# 86_ZigBee.net
KiCad netlist of a schematic drawn in Altium Designer
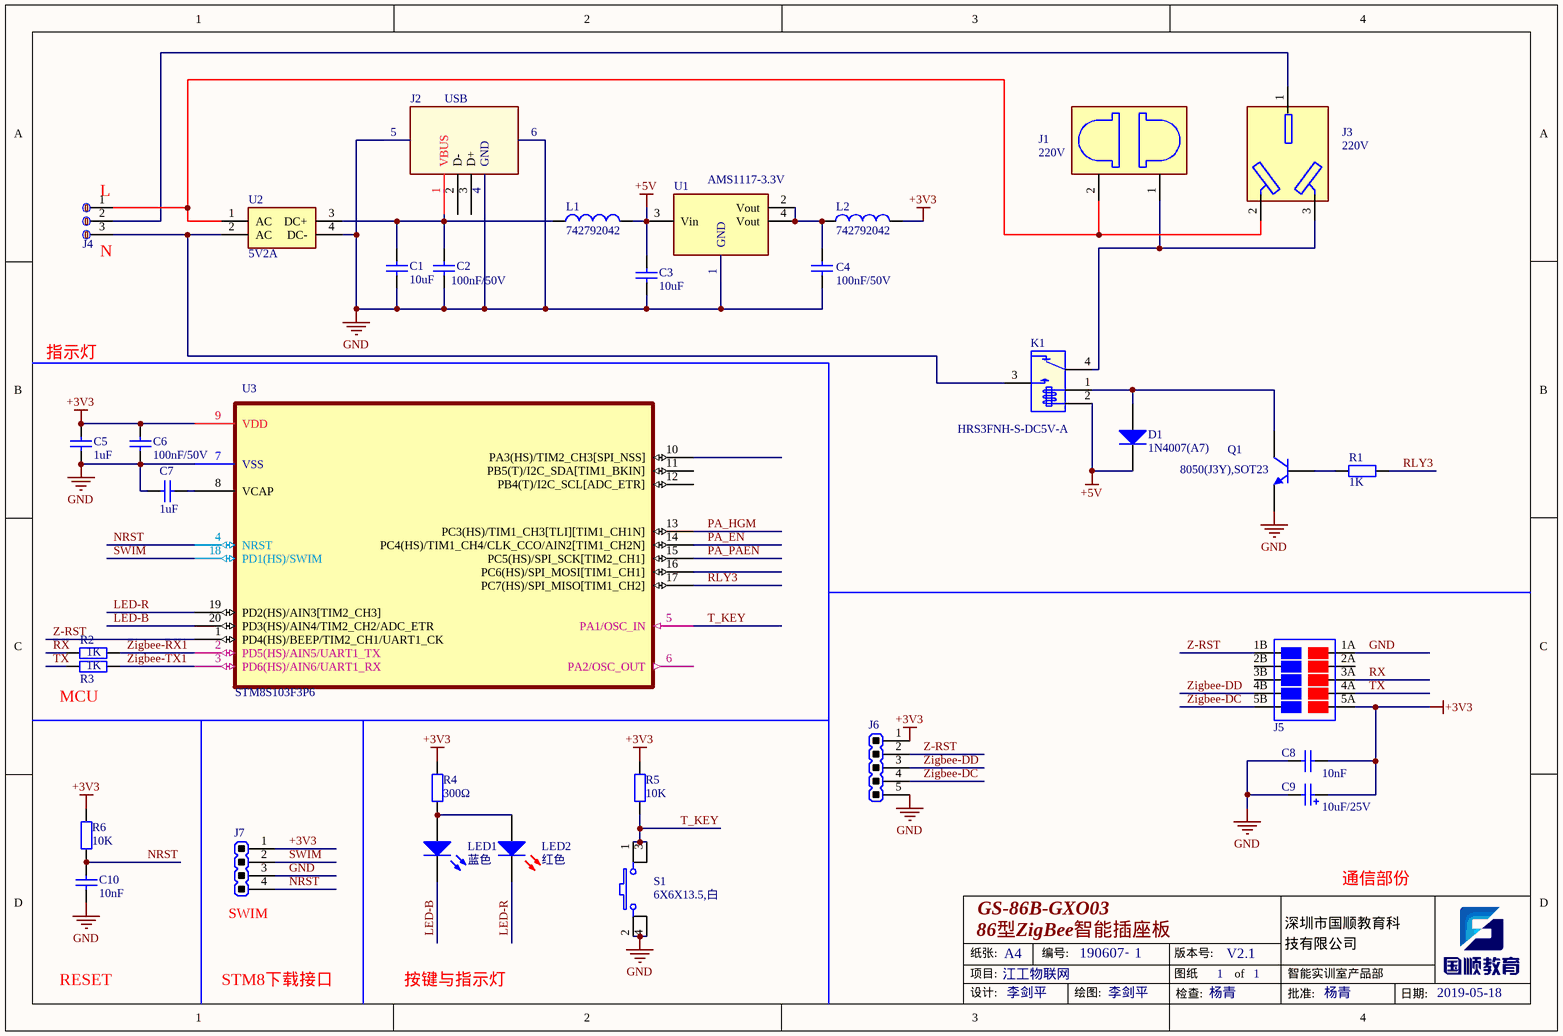
[diagram p0: 86型ZigBee智能插座.SchDoc]

(export (version "E")
  (design (tool "Eeschema 10.0.6"))
  (components
    (comp (ref "C1")
      (value "10uF")
      (footprint "C0603")
      (description "Capacitor")
      (libsource (lib "贴片电容") (part "10uF_16V_0603"))
    )
    (comp (ref "C2")
      (value "100nF/50V")
      (footprint "C0603")
      (description "Capacitor")
      (libsource (lib "贴片电容") (part "100nF_50V_0603"))
    )
    (comp (ref "C3")
      (value "10uF")
      (footprint "C0603")
      (description "Capacitor")
      (libsource (lib "贴片电容") (part "10uF_16V_0603"))
    )
    (comp (ref "C4")
      (value "100nF/50V")
      (footprint "C0603")
      (description "Capacitor")
      (libsource (lib "贴片电容") (part "100nF_50V_0603"))
    )
    (comp (ref "C5")
      (value "1uF")
      (footprint "C0603")
      (description "Capacitor")
      (libsource (lib "贴片电容") (part "1uF_25V_X7R_0603"))
    )
    (comp (ref "C6")
      (value "100nF/50V")
      (footprint "C0603")
      (description "Capacitor")
      (libsource (lib "贴片电容") (part "100nF_50V_0603"))
    )
    (comp (ref "C7")
      (value "1uF")
      (footprint "C0603")
      (description "Capacitor")
      (libsource (lib "贴片电容") (part "1uF_25V_X7R_0603"))
    )
    (comp (ref "C8")
      (value "10nF")
      (footprint "C0603")
      (description "Capacitor")
      (libsource (lib "贴片电容") (part "10nF_16V_0603"))
    )
    (comp (ref "C9")
      (value "10uF/25V")
      (footprint "TC3528X21B")
      (description "钽电容,10uF/25V-3528B")
      (libsource (lib "贴片电容") (part "CAPC-10uF/25V_3528B"))
    )
    (comp (ref "C10")
      (value "10nF")
      (footprint "C0603")
      (description "Capacitor")
      (libsource (lib "贴片电容") (part "10nF_16V_0603"))
    )
    (comp (ref "D1")
      (value "1N4007(A7)")
      (footprint "SOD-123FL")
      (description "1N4007(A7),1A/1000V,SOD-123FL")
      (libsource (lib "二极管") (part "1N4007(A7)_SOD-123FL"))
    )
    (comp (ref "J1")
      (value "220V")
      (footprint "JACK-2 Line")
      (description "PCB板电源插口")
      (libsource (lib "杂项元件") (part "JACK-2 Line"))
    )
    (comp (ref "J2")
      (value "USB")
      (footprint "USB-F-Type A")
      (description "USB-TYPE A 母座")
      (libsource (lib "连接器") (part "USB-AF-17.5"))
    )
    (comp (ref "J3")
      (value "220V")
      (footprint "JACK-3 Line")
      (description "PCB板电源插口")
      (libsource (lib "杂项元件") (part "JACK-3 Line"))
    )
    (comp (ref "J4")
      (value "PILLAR-3P-11.5-(6.5*4.5*8+G4.2*1.5*2)")
      (footprint "PILLAR-3P-11.5-(6.5*4.5*8+G4.2*1.5*2)")
      (description "铜柱接口")
      (libsource (lib "接口") (part "PILLAR-3P-11.5-(6.5*4.5*8+G4.2*1.5*2)"))
    )
    (comp (ref "J5")
      (value "EDGE 10P-2.54/1.0-F")
      (footprint "EDGE 10P-2.54/1.0-F")
      (description "金手指PCB焊接位")
      (libsource (lib "连接器") (part "EDGE 10P-2.54/1.0-F"))
    )
    (comp (ref "J6")
      (value "HDRM-1*5-2.54-AK")
      (footprint "HDRM-1*5-2.54-AK1")
      (description "排针,直")
      (libsource (lib "接口") (part "HDRM-1*5-2.54-AK"))
    )
    (comp (ref "J7")
      (value "HDRM-1*4-2.54-AK")
      (footprint "HDRM-1*4-2.54-AK1")
      (description "排针,直")
      (libsource (lib "接口") (part "HDRM-1*4-2.54-AK"))
    )
    (comp (ref "K1")
      (value "HRS3FNH-S-DC5V-A")
      (footprint "RELAY_HRS3FNH-S-DCxV-A")
      (description "汇港,HRS3FNH-S-DC5V-A,5V,4脚,容量10A,线圈功率0.45W")
      (libsource (lib "杂项元件") (part "RLY_HRS3FNH-S-DC5V-A"))
    )
    (comp (ref "L1")
      (value "742792042")
      (footprint "L0805")
      (description "磁珠,WE-CBF,600@100M,\r\n500Ohm,200mA,0805,742792042")
      (libsource (lib "电感") (part "BEAD-742792042_0805"))
    )
    (comp (ref "L2")
      (value "742792042")
      (footprint "L0805")
      (description "WE-CBF,600@100M,500Ohm,200mA,0805,742792042")
      (libsource (lib "") (part "BEAD-742792042_0805_1"))
    )
    (comp (ref "LED1")
      (value "蓝色")
      (footprint "LED0805-B1")
      (description "0805 LED")
      (libsource (lib "晶体管") (part "LED-蓝_0805"))
    )
    (comp (ref "LED2")
      (value "红色")
      (footprint "LED0805-R1")
      (description "0805 LED")
      (libsource (lib "晶体管") (part "LED-红_0805"))
    )
    (comp (ref "Q1")
      (value "8050(J3Y),SOT23")
      (footprint "SOT23")
      (description "NPN,8050,SOT23")
      (libsource (lib "三极管") (part "NPN_8050(J3Y)_SOT23"))
    )
    (comp (ref "R1")
      (value "1K")
      (footprint "R0603")
      (description "1K,±5%,0603")
      (libsource (lib "") (part "10K_5%_0603_1"))
    )
    (comp (ref "R2")
      (value "1K")
      (footprint "R0603")
      (description "1K,±5%,0603")
      (libsource (lib "贴片电阻") (part "1K_5%_0603"))
    )
    (comp (ref "R3")
      (value "1K")
      (footprint "R0603")
      (description "1K,±5%,0603")
      (libsource (lib "贴片电阻") (part "1K_5%_0603"))
    )
    (comp (ref "R4")
      (value "300Ω")
      (footprint "R0603")
      (description "300Ω,±5%,0603")
      (libsource (lib "贴片电阻") (part "300Ω_5%_0603"))
    )
    (comp (ref "R5")
      (value "10K")
      (footprint "R0603")
      (description "10K,±5%,0603")
      (libsource (lib "贴片电阻") (part "10K_5%_0603"))
    )
    (comp (ref "R6")
      (value "10K")
      (footprint "R0603")
      (description "10K,±5%,0603")
      (libsource (lib "贴片电阻") (part "10K_5%_0603"))
    )
    (comp (ref "S1")
      (value "6X6X13.5,白")
      (footprint "SW2-6.0X6.0X13.5-W")
      (description "6X6X13.5,白,插针")
      (libsource (lib "按键开关") (part "SW-PB_6X6X13.5-4P-W"))
    )
    (comp (ref "U1")
      (value "AMS1117-3.3V")
      (footprint "SOT-223")
      (description "三端稳压器")
      (libsource (lib "IC") (part "AMS1117-3.3V_SOT223"))
    )
    (comp (ref "U2")
      (value "5V2A")
      (footprint "Module_RPD10W")
      (description "AC/DC模块")
      (libsource (lib "杂项元件") (part "Module_RPD10W05E202S"))
    )
    (comp (ref "U3")
      (value "STM8S103F3P6")
      (footprint "TSSOP20-0.65/4.4")
      (description "STM8 ARM-based 32-bit MCU with 8 Kbytes Flash, 20-pin TSSOP, Industrial Temperature")
      (libsource (lib "IC") (part "STM8S103F3P6_TSSOP20"))
    )
  )
  (nets
    (net (code "1") (name "+3V3") (class "Default")
      (node (ref "C5") (pin "2") (pinfunction "2_2") (pintype "passive"))
      (node (ref "C6") (pin "1") (pinfunction "1_1") (pintype "passive"))
      (node (ref "C8") (pin "2") (pinfunction "2_2") (pintype "passive"))
      (node (ref "C9") (pin "1") (pinfunction "1_1") (pintype "passive"))
      (node (ref "J5") (pin "5A") (pinfunction "5A_5A") (pintype "passive"))
      (node (ref "J6") (pin "1") (pinfunction "1_1") (pintype "passive"))
      (node (ref "J7") (pin "1") (pinfunction "1_1") (pintype "passive"))
      (node (ref "L2") (pin "2") (pinfunction "2_2") (pintype "passive"))
      (node (ref "R4") (pin "2") (pinfunction "2_2") (pintype "passive"))
      (node (ref "R5") (pin "1") (pinfunction "1_1") (pintype "passive"))
      (node (ref "R6") (pin "1") (pinfunction "1_1") (pintype "passive"))
      (node (ref "U3") (pin "9") (pinfunction "VDD_9") (pintype "power_in"))
    )
    (net (code "2") (name "+5V") (class "Default")
      (node (ref "C3") (pin "1") (pinfunction "1_1") (pintype "passive"))
      (node (ref "D1") (pin "2") (pinfunction "K_2") (pintype "passive"))
      (node (ref "K1") (pin "2") (pinfunction "COIL2_2") (pintype "passive"))
      (node (ref "L1") (pin "2") (pinfunction "2_2") (pintype "passive"))
      (node (ref "U1") (pin "3") (pinfunction "Vin_3") (pintype "passive"))
    )
    (net (code "3") (name "/LED-B") (class "Default")
      (node (ref "LED1") (pin "2") (pinfunction "K_2") (pintype "passive"))
      (node (ref "U3") (pin "20") (pinfunction "PD3(HS)/AIN4/TIM2_CH2/ADC_ETR_20") (pintype "bidirectional"))
    )
    (net (code "4") (name "/LED-R") (class "Default")
      (node (ref "LED2") (pin "2") (pinfunction "K_2") (pintype "passive"))
      (node (ref "U3") (pin "19") (pinfunction "PD2(HS)/AIN3[TIM2_CH3]_19") (pintype "bidirectional"))
    )
    (net (code "5") (name "/NRST") (class "Default")
      (node (ref "C10") (pin "2") (pinfunction "2_2") (pintype "passive"))
      (node (ref "J7") (pin "4") (pinfunction "4_4") (pintype "passive"))
      (node (ref "R6") (pin "2") (pinfunction "2_2") (pintype "passive"))
      (node (ref "U3") (pin "4") (pinfunction "NRST_4") (pintype "bidirectional"))
    )
    (net (code "6") (name "/PA_EN") (class "Default")
      (node (ref "U3") (pin "14") (pinfunction "PC4(HS)/TIM1_CH4/CLK_CCO/AIN2[TIM1_CH2N]_14") (pintype "bidirectional"))
    )
    (net (code "7") (name "/PA_HGM") (class "Default")
      (node (ref "U3") (pin "13") (pinfunction "PC3(HS)/TIM1_CH3[TLI][TIM1_CH1N]_13") (pintype "bidirectional"))
    )
    (net (code "8") (name "/PA_PAEN") (class "Default")
      (node (ref "U3") (pin "15") (pinfunction "PC5(HS)/SPI_SCK[TIM2_CH1]_15") (pintype "bidirectional"))
    )
    (net (code "9") (name "/RLY3") (class "Default")
      (node (ref "R1") (pin "2") (pinfunction "2_2") (pintype "passive"))
      (node (ref "U3") (pin "17") (pinfunction "PC7(HS)/SPI_MISO[TIM1_CH2]_17") (pintype "bidirectional"))
    )
    (net (code "10") (name "/RX") (class "Default")
      (node (ref "J5") (pin "3A") (pinfunction "3A_3A") (pintype "passive"))
      (node (ref "R2") (pin "1") (pinfunction "1_1") (pintype "passive"))
    )
    (net (code "11") (name "/SWIM") (class "Default")
      (node (ref "J7") (pin "2") (pinfunction "2_2") (pintype "passive"))
      (node (ref "U3") (pin "18") (pinfunction "PD1(HS)/SWIM_18") (pintype "bidirectional"))
    )
    (net (code "12") (name "/TX") (class "Default")
      (node (ref "J5") (pin "4A") (pinfunction "4A_4A") (pintype "passive"))
      (node (ref "R3") (pin "1") (pinfunction "1_1") (pintype "passive"))
    )
    (net (code "13") (name "/T_KEY") (class "Default")
      (node (ref "R5") (pin "2") (pinfunction "2_2") (pintype "passive"))
      (node (ref "S1") (pin "1") (pinfunction "1_1") (pintype "passive"))
      (node (ref "S1") (pin "3") (pinfunction "3_3") (pintype "passive"))
      (node (ref "U3") (pin "5") (pinfunction "PA1/OSC_IN_5") (pintype "input"))
    )
    (net (code "14") (name "/Z-RST") (class "Default")
      (node (ref "J5") (pin "1B") (pinfunction "1B_1B") (pintype "passive"))
      (node (ref "J6") (pin "2") (pinfunction "2_2") (pintype "passive"))
      (node (ref "U3") (pin "1") (pinfunction "PD4(HS)/BEEP/TIM2_CH1/UART1_CK_1") (pintype "bidirectional"))
    )
    (net (code "15") (name "/Zigbee-DC") (class "Default")
      (node (ref "J5") (pin "5B") (pinfunction "5B_5B") (pintype "passive"))
      (node (ref "J6") (pin "4") (pinfunction "4_4") (pintype "passive"))
    )
    (net (code "16") (name "/Zigbee-DD") (class "Default")
      (node (ref "J5") (pin "4B") (pinfunction "4B_4B") (pintype "passive"))
      (node (ref "J6") (pin "3") (pinfunction "3_3") (pintype "passive"))
    )
    (net (code "17") (name "/Zigbee-RX1") (class "Default")
      (node (ref "R2") (pin "2") (pinfunction "2_2") (pintype "passive"))
      (node (ref "U3") (pin "2") (pinfunction "PD5(HS)/AIN5/UART1_TX_2") (pintype "bidirectional"))
    )
    (net (code "18") (name "/Zigbee-TX1") (class "Default")
      (node (ref "R3") (pin "2") (pinfunction "2_2") (pintype "passive"))
      (node (ref "U3") (pin "3") (pinfunction "PD6(HS)/AIN6/UART1_RX_3") (pintype "bidirectional"))
    )
    (net (code "19") (name "GND") (class "Default")
      (node (ref "C1") (pin "2") (pinfunction "2_2") (pintype "passive"))
      (node (ref "C10") (pin "1") (pinfunction "1_1") (pintype "passive"))
      (node (ref "C2") (pin "2") (pinfunction "2_2") (pintype "passive"))
      (node (ref "C3") (pin "2") (pinfunction "2_2") (pintype "passive"))
      (node (ref "C4") (pin "2") (pinfunction "2_2") (pintype "passive"))
      (node (ref "C5") (pin "1") (pinfunction "1_1") (pintype "passive"))
      (node (ref "C6") (pin "2") (pinfunction "2_2") (pintype "passive"))
      (node (ref "C7") (pin "2") (pinfunction "2_2") (pintype "passive"))
      (node (ref "C8") (pin "1") (pinfunction "1_1") (pintype "passive"))
      (node (ref "C9") (pin "2") (pinfunction "2_2") (pintype "passive"))
      (node (ref "J2") (pin "4") (pinfunction "GND_4") (pintype "passive"))
      (node (ref "J2") (pin "5") (pinfunction "5_5") (pintype "passive"))
      (node (ref "J2") (pin "6") (pinfunction "6_6") (pintype "passive"))
      (node (ref "J5") (pin "1A") (pinfunction "1A_1A") (pintype "passive"))
      (node (ref "J6") (pin "5") (pinfunction "5_5") (pintype "passive"))
      (node (ref "J7") (pin "3") (pinfunction "3_3") (pintype "passive"))
      (node (ref "Q1") (pin "2") (pinfunction "E_2") (pintype "passive"))
      (node (ref "S1") (pin "2") (pinfunction "2_2") (pintype "passive"))
      (node (ref "S1") (pin "4") (pinfunction "4_4") (pintype "passive"))
      (node (ref "U1") (pin "1") (pinfunction "GND_1") (pintype "passive"))
      (node (ref "U2") (pin "4") (pinfunction "DC-_4") (pintype "passive"))
      (node (ref "U3") (pin "7") (pinfunction "VSS_7") (pintype "power_in"))
    )
    (net (code "20") (name "Net-(C4-Pad1)") (class "Default")
      (node (ref "C4") (pin "1") (pinfunction "1_1") (pintype "passive"))
      (node (ref "L2") (pin "1") (pinfunction "1_1") (pintype "passive"))
      (node (ref "U1") (pin "2") (pinfunction "Vout_2") (pintype "passive"))
      (node (ref "U1") (pin "4") (pinfunction "Vout_4") (pintype "passive"))
    )
    (net (code "21") (name "Net-(D1-A)") (class "Default")
      (node (ref "D1") (pin "1") (pinfunction "A_1") (pintype "passive"))
      (node (ref "K1") (pin "1") (pinfunction "COIL1_1") (pintype "passive"))
      (node (ref "Q1") (pin "3") (pinfunction "C_3") (pintype "passive"))
    )
    (net (code "22") (name "Net-(J1-Pad2)") (class "Default")
      (node (ref "J1") (pin "2") (pinfunction "2_2") (pintype "passive"))
      (node (ref "J3") (pin "2") (pinfunction "2_2") (pintype "passive"))
      (node (ref "J4") (pin "1") (pinfunction "1_1") (pintype "passive"))
      (node (ref "U2") (pin "1") (pinfunction "AC_1") (pintype "passive"))
    )
    (net (code "23") (name "Net-(J2-VBUS)") (class "Default")
      (node (ref "C1") (pin "1") (pinfunction "1_1") (pintype "passive"))
      (node (ref "C2") (pin "1") (pinfunction "1_1") (pintype "passive"))
      (node (ref "J2") (pin "1") (pinfunction "VBUS_1") (pintype "passive"))
      (node (ref "L1") (pin "1") (pinfunction "1_1") (pintype "passive"))
      (node (ref "U2") (pin "3") (pinfunction "DC+_3") (pintype "passive"))
    )
    (net (code "24") (name "Net-(J3-Pad1)") (class "Default")
      (node (ref "J3") (pin "1") (pinfunction "1_1") (pintype "passive"))
      (node (ref "J4") (pin "2") (pinfunction "2_2") (pintype "passive"))
    )
    (net (code "25") (name "Net-(K1-COM)") (class "Default")
      (node (ref "J1") (pin "1") (pinfunction "1_1") (pintype "passive"))
      (node (ref "J3") (pin "3") (pinfunction "3_3") (pintype "passive"))
      (node (ref "K1") (pin "4") (pinfunction "COM_4") (pintype "passive"))
    )
    (net (code "26") (name "Net-(K1-NO)") (class "Default")
      (node (ref "J4") (pin "3") (pinfunction "3_3") (pintype "passive"))
      (node (ref "K1") (pin "3") (pinfunction "NO_3") (pintype "passive"))
      (node (ref "U2") (pin "2") (pinfunction "AC_2") (pintype "passive"))
    )
    (net (code "27") (name "Net-(LED1-A)") (class "Default")
      (node (ref "LED1") (pin "1") (pinfunction "A_1") (pintype "passive"))
      (node (ref "LED2") (pin "1") (pinfunction "A_1") (pintype "passive"))
      (node (ref "R4") (pin "1") (pinfunction "1_1") (pintype "passive"))
    )
    (net (code "28") (name "Net-(Q1-B)") (class "Default")
      (node (ref "Q1") (pin "1") (pinfunction "B_1") (pintype "passive"))
      (node (ref "R1") (pin "1") (pinfunction "1_1") (pintype "passive"))
    )
    (net (code "29") (name "Net-(U3-VCAP)") (class "Default")
      (node (ref "C7") (pin "1") (pinfunction "1_1") (pintype "passive"))
      (node (ref "U3") (pin "8") (pinfunction "VCAP_8") (pintype "passive"))
    )
    (net (code "30") (name "unconnected-(J2-D+-Pad3)") (class "Default")
      (node (ref "J2") (pin "3") (pinfunction "D+_3") (pintype "passive"))
    )
    (net (code "31") (name "unconnected-(J2-D--Pad2)") (class "Default")
      (node (ref "J2") (pin "2") (pinfunction "D-_2") (pintype "passive"))
    )
    (net (code "32") (name "unconnected-(J5-Pad2A)") (class "Default")
      (node (ref "J5") (pin "2A") (pinfunction "2A_2A") (pintype "passive"))
    )
    (net (code "33") (name "unconnected-(J5-Pad2B)") (class "Default")
      (node (ref "J5") (pin "2B") (pinfunction "2B_2B") (pintype "passive"))
    )
    (net (code "34") (name "unconnected-(J5-Pad3B)") (class "Default")
      (node (ref "J5") (pin "3B") (pinfunction "3B_3B") (pintype "passive"))
    )
    (net (code "35") (name "unconnected-(U3-PA2{slash}OSC_OUT-Pad6)") (class "Default")
      (node (ref "U3") (pin "6") (pinfunction "PA2/OSC_OUT_6") (pintype "output"))
    )
    (net (code "36") (name "unconnected-(U3-PA3(HS){slash}TIM2_CH3[SPI_NSS]-Pad10)") (class "Default")
      (node (ref "U3") (pin "10") (pinfunction "PA3(HS)/TIM2_CH3[SPI_NSS]_10") (pintype "bidirectional"))
    )
    (net (code "37") (name "unconnected-(U3-PB4(T){slash}I2C_SCL[ADC_ETR]-Pad12)") (class "Default")
      (node (ref "U3") (pin "12") (pinfunction "PB4(T)/I2C_SCL[ADC_ETR]_12") (pintype "bidirectional"))
    )
    (net (code "38") (name "unconnected-(U3-PB5(T){slash}I2C_SDA[TIM1_BKIN]-Pad11)") (class "Default")
      (node (ref "U3") (pin "11") (pinfunction "PB5(T)/I2C_SDA[TIM1_BKIN]_11") (pintype "bidirectional"))
    )
    (net (code "39") (name "unconnected-(U3-PC6(HS){slash}SPI_MOSI[TIM1_CH1]-Pad16)") (class "Default")
      (node (ref "U3") (pin "16") (pinfunction "PC6(HS)/SPI_MOSI[TIM1_CH1]_16") (pintype "bidirectional"))
    )
  )
)
